# Orsini.net
KiCad netlist of a schematic drawn in EAGLE
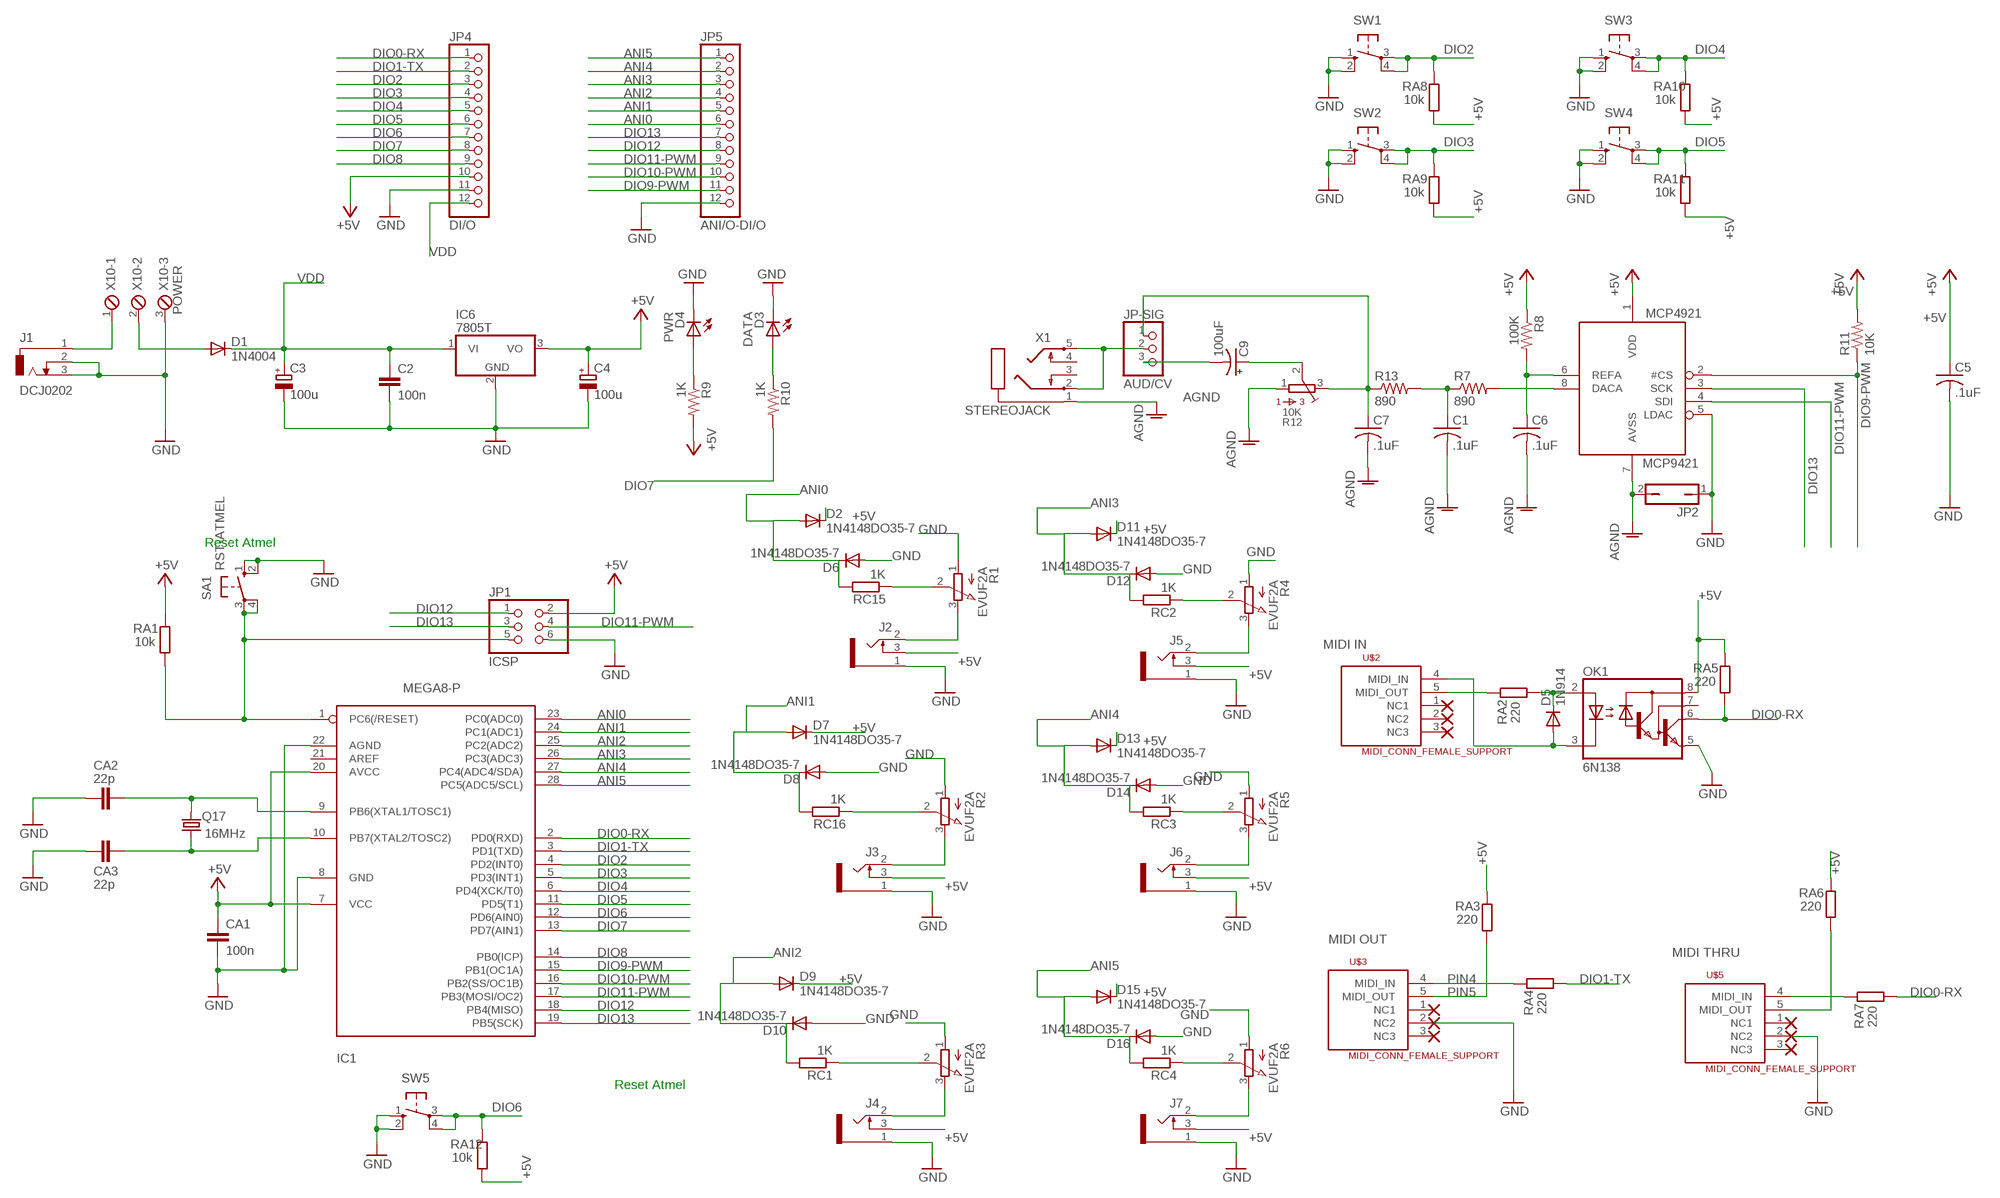
[diagram p0: schematic, sheet 1]

(export (version "E")
  (design (tool "Eeschema 10.0.6"))
  (components
    (comp (ref "C1")
      (value ".1uF")
      (footprint "eagle-import:C050-025X075")
      (libsource (lib "eagle-import") (part "C-US050-025X075"))
    )
    (comp (ref "C2")
      (value "100n")
      (footprint "eagle-import:C050-025X075")
      (libsource (lib "eagle-import") (part "C-EU050-025X075"))
    )
    (comp (ref "C3")
      (value "100u")
      (footprint "eagle-import:E2,5-7")
      (libsource (lib "eagle-import") (part "CPOL-EUE2.5-7"))
    )
    (comp (ref "C4")
      (value "100u")
      (footprint "eagle-import:E2,5-7")
      (libsource (lib "eagle-import") (part "CPOL-EUE2.5-7"))
    )
    (comp (ref "C5")
      (value ".1uF")
      (footprint "eagle-import:C025-025X050")
      (libsource (lib "eagle-import") (part "C-US025-025X050"))
    )
    (comp (ref "C6")
      (value ".1uF")
      (footprint "eagle-import:C025-025X050")
      (libsource (lib "eagle-import") (part "C-US025-025X050"))
    )
    (comp (ref "C7")
      (value ".1uF")
      (footprint "eagle-import:C050-025X075")
      (libsource (lib "eagle-import") (part "C-US050-025X075"))
    )
    (comp (ref "C9")
      (value "100uF")
      (footprint "eagle-import:E2,5-5")
      (libsource (lib "eagle-import") (part "CPOL-USE2.5-5"))
    )
    (comp (ref "CA1")
      (value "100n")
      (footprint "eagle-import:C050-025X075")
      (libsource (lib "eagle-import") (part "C-EU050-025X075"))
    )
    (comp (ref "CA2")
      (value "22p")
      (footprint "eagle-import:C050-025X075")
      (libsource (lib "eagle-import") (part "C-EU050-025X075"))
    )
    (comp (ref "CA3")
      (value "22p")
      (footprint "eagle-import:C050-025X075")
      (libsource (lib "eagle-import") (part "C-EU050-025X075"))
    )
    (comp (ref "D1")
      (value "1N4004")
      (footprint "eagle-import:DO41-10")
      (libsource (lib "eagle-import") (part "1N4004"))
    )
    (comp (ref "D2")
      (value "1N4148DO35-7")
      (footprint "eagle-import:DO35-7")
      (libsource (lib "eagle-import") (part "1N4148DO35-7"))
    )
    (comp (ref "D3")
      (value "DATA")
      (footprint "eagle-import:LED4MM")
      (libsource (lib "eagle-import") (part "HLMP-M"))
    )
    (comp (ref "D4")
      (value "PWR")
      (footprint "eagle-import:LED4MM")
      (libsource (lib "eagle-import") (part "HLMP-M"))
    )
    (comp (ref "D5")
      (value "1N914")
      (footprint "eagle-import:DO34-7")
      (libsource (lib "eagle-import") (part "BAS15"))
    )
    (comp (ref "D6")
      (value "1N4148DO35-7")
      (footprint "eagle-import:DO35-7")
      (libsource (lib "eagle-import") (part "1N4148DO35-7"))
    )
    (comp (ref "D7")
      (value "1N4148DO35-7")
      (footprint "eagle-import:DO35-7")
      (libsource (lib "eagle-import") (part "1N4148DO35-7"))
    )
    (comp (ref "D8")
      (value "1N4148DO35-7")
      (footprint "eagle-import:DO35-7")
      (libsource (lib "eagle-import") (part "1N4148DO35-7"))
    )
    (comp (ref "D9")
      (value "1N4148DO35-7")
      (footprint "eagle-import:DO35-7")
      (libsource (lib "eagle-import") (part "1N4148DO35-7"))
    )
    (comp (ref "D10")
      (value "1N4148DO35-7")
      (footprint "eagle-import:DO35-7")
      (libsource (lib "eagle-import") (part "1N4148DO35-7"))
    )
    (comp (ref "D11")
      (value "1N4148DO35-7")
      (footprint "eagle-import:DO35-7")
      (libsource (lib "eagle-import") (part "1N4148DO35-7"))
    )
    (comp (ref "D12")
      (value "1N4148DO35-7")
      (footprint "eagle-import:DO35-7")
      (libsource (lib "eagle-import") (part "1N4148DO35-7"))
    )
    (comp (ref "D13")
      (value "1N4148DO35-7")
      (footprint "eagle-import:DO35-7")
      (libsource (lib "eagle-import") (part "1N4148DO35-7"))
    )
    (comp (ref "D14")
      (value "1N4148DO35-7")
      (footprint "eagle-import:DO35-7")
      (libsource (lib "eagle-import") (part "1N4148DO35-7"))
    )
    (comp (ref "D15")
      (value "1N4148DO35-7")
      (footprint "eagle-import:DO35-7")
      (libsource (lib "eagle-import") (part "1N4148DO35-7"))
    )
    (comp (ref "D16")
      (value "1N4148DO35-7")
      (footprint "eagle-import:DO35-7")
      (libsource (lib "eagle-import") (part "1N4148DO35-7"))
    )
    (comp (ref "IC1")
      (value "MEGA8-P")
      (footprint "eagle-import:DIL28-3")
      (libsource (lib "eagle-import") (part "MEGA8-P"))
    )
    (comp (ref "IC6")
      (value "7805T")
      (footprint "eagle-import:TO220H")
      (libsource (lib "eagle-import") (part "78T05"))
    )
    (comp (ref "J1")
      (value "DCJ0202")
      (footprint "eagle-import:DCJ0202")
      (libsource (lib "eagle-import") (part "DCJ0202"))
    )
    (comp (ref "J2")
      (value "1502_03SLOTTED")
      (footprint "eagle-import:1502_03_SLOTTED")
      (libsource (lib "eagle-import") (part "1502_03SLOTTED"))
    )
    (comp (ref "J3")
      (value "1502_03SLOTTED")
      (footprint "eagle-import:1502_03_SLOTTED")
      (libsource (lib "eagle-import") (part "1502_03SLOTTED"))
    )
    (comp (ref "J4")
      (value "1502_03SLOTTED")
      (footprint "eagle-import:1502_03_SLOTTED")
      (libsource (lib "eagle-import") (part "1502_03SLOTTED"))
    )
    (comp (ref "J5")
      (value "1502_03SLOTTED")
      (footprint "eagle-import:1502_03_SLOTTED")
      (libsource (lib "eagle-import") (part "1502_03SLOTTED"))
    )
    (comp (ref "J6")
      (value "1502_03SLOTTED")
      (footprint "eagle-import:1502_03_SLOTTED")
      (libsource (lib "eagle-import") (part "1502_03SLOTTED"))
    )
    (comp (ref "J7")
      (value "1502_03SLOTTED")
      (footprint "eagle-import:1502_03_SLOTTED")
      (libsource (lib "eagle-import") (part "1502_03SLOTTED"))
    )
    (comp (ref "JP-SIG")
      (value "AUD/CV")
      (footprint "eagle-import:1X03")
      (libsource (lib "eagle-import") (part "PINHD-1X3"))
    )
    (comp (ref "JP1")
      (value "ICSP")
      (footprint "eagle-import:2X03")
      (libsource (lib "eagle-import") (part "PINHD-2X3"))
    )
    (comp (ref "JP2")
      (value "JP1Q")
      (footprint "eagle-import:JP1")
      (libsource (lib "eagle-import") (part "JP1Q"))
    )
    (comp (ref "JP4")
      (value "DI/O")
      (footprint "eagle-import:1X12")
      (libsource (lib "eagle-import") (part "PINHD-1X12"))
    )
    (comp (ref "JP5")
      (value "ANI/O-DI/O")
      (footprint "eagle-import:1X12")
      (libsource (lib "eagle-import") (part "PINHD-1X12"))
    )
    (comp (ref "MCP4921")
      (value "MCP9421")
      (footprint "eagle-import:DIL08")
      (libsource (lib "eagle-import") (part "MCP9421"))
    )
    (comp (ref "OK1")
      (value "6N138")
      (footprint "eagle-import:DIL08")
      (fields (field (name "MF") "VISHAY/TELEFUNKEN"))
      (libsource (lib "eagle-import") (part "6N138"))
    )
    (comp (ref "Q17")
      (value "16MHz")
      (footprint "eagle-import:HC49_S")
      (libsource (lib "eagle-import") (part "CRYSTALHC49S"))
    )
    (comp (ref "R1")
      (value "EVUF2A")
      (footprint "eagle-import:EVUF")
      (libsource (lib "eagle-import") (part "EVUAF2"))
    )
    (comp (ref "R2")
      (value "EVUF2A")
      (footprint "eagle-import:EVUF")
      (libsource (lib "eagle-import") (part "EVUAF2"))
    )
    (comp (ref "R3")
      (value "EVUF2A")
      (footprint "eagle-import:EVUF")
      (libsource (lib "eagle-import") (part "EVUAF2"))
    )
    (comp (ref "R4")
      (value "EVUF2A")
      (footprint "eagle-import:EVUF")
      (libsource (lib "eagle-import") (part "EVUAF2"))
    )
    (comp (ref "R5")
      (value "EVUF2A")
      (footprint "eagle-import:EVUF")
      (libsource (lib "eagle-import") (part "EVUAF2"))
    )
    (comp (ref "R6")
      (value "EVUF2A")
      (footprint "eagle-import:EVUF")
      (libsource (lib "eagle-import") (part "EVUAF2"))
    )
    (comp (ref "R7")
      (value "890")
      (footprint "eagle-import:0207_7")
      (libsource (lib "eagle-import") (part "R-US_0207/7"))
    )
    (comp (ref "R8")
      (value "100K")
      (footprint "eagle-import:0207_7")
      (libsource (lib "eagle-import") (part "R-US_0207/7"))
    )
    (comp (ref "R9")
      (value "1K")
      (footprint "eagle-import:0207_7")
      (libsource (lib "eagle-import") (part "R-US_0207/7"))
    )
    (comp (ref "R10")
      (value "1K")
      (footprint "eagle-import:0207_7")
      (libsource (lib "eagle-import") (part "R-US_0207/7"))
    )
    (comp (ref "R11")
      (value "10K")
      (footprint "eagle-import:0207_10")
      (libsource (lib "eagle-import") (part "R-US_0207/10"))
    )
    (comp (ref "R12")
      (value "10K")
      (footprint "eagle-import:3386F")
      (libsource (lib "eagle-import") (part "3386-F"))
    )
    (comp (ref "R13")
      (value "890")
      (footprint "eagle-import:0207_7")
      (libsource (lib "eagle-import") (part "R-US_0207/7"))
    )
    (comp (ref "RA1")
      (value "10k")
      (footprint "eagle-import:0207_10")
      (libsource (lib "eagle-import") (part "R-EU_0207/10"))
    )
    (comp (ref "RA2")
      (value "220")
      (footprint "eagle-import:0207_10")
      (libsource (lib "eagle-import") (part "R-EU_0207/10"))
    )
    (comp (ref "RA3")
      (value "220")
      (footprint "eagle-import:0207_10")
      (libsource (lib "eagle-import") (part "R-EU_0207/10"))
    )
    (comp (ref "RA4")
      (value "220")
      (footprint "eagle-import:0207_10")
      (libsource (lib "eagle-import") (part "R-EU_0207/10"))
    )
    (comp (ref "RA5")
      (value "220")
      (footprint "eagle-import:0207_10")
      (libsource (lib "eagle-import") (part "R-EU_0207/10"))
    )
    (comp (ref "RA6")
      (value "220")
      (footprint "eagle-import:0207_10")
      (libsource (lib "eagle-import") (part "R-EU_0207/10"))
    )
    (comp (ref "RA7")
      (value "220")
      (footprint "eagle-import:0207_10")
      (libsource (lib "eagle-import") (part "R-EU_0207/10"))
    )
    (comp (ref "RA8")
      (value "10k")
      (footprint "eagle-import:0207_10")
      (libsource (lib "eagle-import") (part "R-EU_0207/10"))
    )
    (comp (ref "RA9")
      (value "10k")
      (footprint "eagle-import:0207_10")
      (libsource (lib "eagle-import") (part "R-EU_0207/10"))
    )
    (comp (ref "RA10")
      (value "10k")
      (footprint "eagle-import:0207_10")
      (libsource (lib "eagle-import") (part "R-EU_0207/10"))
    )
    (comp (ref "RA11")
      (value "10k")
      (footprint "eagle-import:0207_10")
      (libsource (lib "eagle-import") (part "R-EU_0207/10"))
    )
    (comp (ref "RA12")
      (value "10k")
      (footprint "eagle-import:0207_10")
      (libsource (lib "eagle-import") (part "R-EU_0207/10"))
    )
    (comp (ref "RC1")
      (value "1K")
      (footprint "eagle-import:0207_10")
      (libsource (lib "eagle-import") (part "R-EU_0207/10"))
    )
    (comp (ref "RC2")
      (value "1K")
      (footprint "eagle-import:0207_10")
      (libsource (lib "eagle-import") (part "R-EU_0207/10"))
    )
    (comp (ref "RC3")
      (value "1K")
      (footprint "eagle-import:0207_10")
      (libsource (lib "eagle-import") (part "R-EU_0207/10"))
    )
    (comp (ref "RC4")
      (value "1K")
      (footprint "eagle-import:0207_10")
      (libsource (lib "eagle-import") (part "R-EU_0207/10"))
    )
    (comp (ref "RC15")
      (value "1K")
      (footprint "eagle-import:0207_10")
      (libsource (lib "eagle-import") (part "R-EU_0207/10"))
    )
    (comp (ref "RC16")
      (value "1K")
      (footprint "eagle-import:0207_10")
      (libsource (lib "eagle-import") (part "R-EU_0207/10"))
    )
    (comp (ref "SA1")
      (value "RST-ATMEL")
      (footprint "eagle-import:B3F-10XX")
      (libsource (lib "eagle-import") (part "10-XX"))
    )
    (comp (ref "SW1")
      (value "40-XX")
      (footprint "eagle-import:B3F-40XX")
      (libsource (lib "eagle-import") (part "40-XX"))
    )
    (comp (ref "SW2")
      (value "40-XX")
      (footprint "eagle-import:B3F-40XX")
      (libsource (lib "eagle-import") (part "40-XX"))
    )
    (comp (ref "SW3")
      (value "40-XX")
      (footprint "eagle-import:B3F-40XX")
      (libsource (lib "eagle-import") (part "40-XX"))
    )
    (comp (ref "SW4")
      (value "40-XX")
      (footprint "eagle-import:B3F-40XX")
      (libsource (lib "eagle-import") (part "40-XX"))
    )
    (comp (ref "SW5")
      (value "40-XX")
      (footprint "eagle-import:B3F-40XX")
      (libsource (lib "eagle-import") (part "40-XX"))
    )
    (comp (ref "U$2")
      (value "MIDI_CONN_FEMALE_SUPPORT")
      (footprint "eagle-import:DIN_5_FEMALE_SUPPORT")
      (libsource (lib "eagle-import") (part "MIDI_CONN_FEMALE_SUPPORT"))
    )
    (comp (ref "U$3")
      (value "MIDI_CONN_FEMALE_SUPPORT")
      (footprint "eagle-import:DIN_5_FEMALE_SUPPORT")
      (libsource (lib "eagle-import") (part "MIDI_CONN_FEMALE_SUPPORT"))
    )
    (comp (ref "U$5")
      (value "MIDI_CONN_FEMALE_SUPPORT")
      (footprint "eagle-import:DIN_5_FEMALE_SUPPORT")
      (libsource (lib "eagle-import") (part "MIDI_CONN_FEMALE_SUPPORT"))
    )
    (comp (ref "X1")
      (value "STEREOJACK")
      (footprint "eagle-import:STX3001")
      (libsource (lib "eagle-import") (part "STEREOJACK"))
    )
    (comp (ref "X10")
      (value "POWER")
      (footprint "eagle-import:3POL254")
      (libsource (lib "eagle-import") (part "MPT3"))
    )
  )
  (nets
    (net (code "1") (name "+5V") (class "Default")
      (node (ref "C4") (pin "+") (pinfunction "+_+") (pintype "passive"))
      (node (ref "C5") (pin "1") (pinfunction "1_1") (pintype "passive"))
      (node (ref "CA1") (pin "1") (pinfunction "1_1") (pintype "passive"))
      (node (ref "D11") (pin "C") (pinfunction "C_C") (pintype "passive"))
      (node (ref "D13") (pin "C") (pinfunction "C_C") (pintype "passive"))
      (node (ref "D15") (pin "C") (pinfunction "C_C") (pintype "passive"))
      (node (ref "D2") (pin "C") (pinfunction "C_C") (pintype "passive"))
      (node (ref "D7") (pin "C") (pinfunction "C_C") (pintype "passive"))
      (node (ref "D9") (pin "C") (pinfunction "C_C") (pintype "passive"))
      (node (ref "IC1") (pin "20") (pinfunction "AVCC_20") (pintype "power_in"))
      (node (ref "IC1") (pin "7") (pinfunction "VCC_7") (pintype "power_in"))
      (node (ref "IC6") (pin "3") (pinfunction "VO_3") (pintype "passive"))
      (node (ref "J2") (pin "3") (pinfunction "3_3") (pintype "passive"))
      (node (ref "J3") (pin "3") (pinfunction "3_3") (pintype "passive"))
      (node (ref "J4") (pin "3") (pinfunction "3_3") (pintype "passive"))
      (node (ref "J5") (pin "3") (pinfunction "3_3") (pintype "passive"))
      (node (ref "J6") (pin "3") (pinfunction "3_3") (pintype "passive"))
      (node (ref "J7") (pin "3") (pinfunction "3_3") (pintype "passive"))
      (node (ref "JP1") (pin "2") (pinfunction "2_2") (pintype "passive"))
      (node (ref "JP4") (pin "10") (pinfunction "10_10") (pintype "passive"))
      (node (ref "MCP4921") (pin "1") (pinfunction "VDD_1") (pintype "power_in"))
      (node (ref "OK1") (pin "8") (pinfunction "VCC_8") (pintype "passive"))
      (node (ref "R11") (pin "2") (pinfunction "2_2") (pintype "passive"))
      (node (ref "R8") (pin "1") (pinfunction "1_1") (pintype "passive"))
      (node (ref "R9") (pin "2") (pinfunction "2_2") (pintype "passive"))
      (node (ref "RA1") (pin "1") (pinfunction "1_1") (pintype "passive"))
      (node (ref "RA10") (pin "2") (pinfunction "2_2") (pintype "passive"))
      (node (ref "RA11") (pin "2") (pinfunction "2_2") (pintype "passive"))
      (node (ref "RA12") (pin "2") (pinfunction "2_2") (pintype "passive"))
      (node (ref "RA3") (pin "1") (pinfunction "1_1") (pintype "passive"))
      (node (ref "RA5") (pin "1") (pinfunction "1_1") (pintype "passive"))
      (node (ref "RA6") (pin "1") (pinfunction "1_1") (pintype "passive"))
      (node (ref "RA8") (pin "2") (pinfunction "2_2") (pintype "passive"))
      (node (ref "RA9") (pin "2") (pinfunction "2_2") (pintype "passive"))
    )
    (net (code "2") (name "/ANI0") (class "Default")
      (node (ref "D2") (pin "A") (pinfunction "A_A") (pintype "passive"))
      (node (ref "D6") (pin "C") (pinfunction "C_C") (pintype "passive"))
      (node (ref "IC1") (pin "23") (pinfunction "PC0(ADC0)_23") (pintype "bidirectional"))
      (node (ref "JP5") (pin "6") (pinfunction "6_6") (pintype "passive"))
      (node (ref "RC15") (pin "2") (pinfunction "2_2") (pintype "passive"))
    )
    (net (code "3") (name "/ANI1") (class "Default")
      (node (ref "D7") (pin "A") (pinfunction "A_A") (pintype "passive"))
      (node (ref "D8") (pin "C") (pinfunction "C_C") (pintype "passive"))
      (node (ref "IC1") (pin "24") (pinfunction "PC1(ADC1)_24") (pintype "bidirectional"))
      (node (ref "JP5") (pin "5") (pinfunction "5_5") (pintype "passive"))
      (node (ref "RC16") (pin "2") (pinfunction "2_2") (pintype "passive"))
    )
    (net (code "4") (name "/ANI2") (class "Default")
      (node (ref "D10") (pin "C") (pinfunction "C_C") (pintype "passive"))
      (node (ref "D9") (pin "A") (pinfunction "A_A") (pintype "passive"))
      (node (ref "IC1") (pin "25") (pinfunction "PC2(ADC2)_25") (pintype "bidirectional"))
      (node (ref "JP5") (pin "4") (pinfunction "4_4") (pintype "passive"))
      (node (ref "RC1") (pin "2") (pinfunction "2_2") (pintype "passive"))
    )
    (net (code "5") (name "/ANI3") (class "Default")
      (node (ref "D11") (pin "A") (pinfunction "A_A") (pintype "passive"))
      (node (ref "D12") (pin "C") (pinfunction "C_C") (pintype "passive"))
      (node (ref "IC1") (pin "26") (pinfunction "PC3(ADC3)_26") (pintype "bidirectional"))
      (node (ref "JP5") (pin "3") (pinfunction "3_3") (pintype "passive"))
      (node (ref "RC2") (pin "2") (pinfunction "2_2") (pintype "passive"))
    )
    (net (code "6") (name "/ANI4") (class "Default")
      (node (ref "D13") (pin "A") (pinfunction "A_A") (pintype "passive"))
      (node (ref "D14") (pin "C") (pinfunction "C_C") (pintype "passive"))
      (node (ref "IC1") (pin "27") (pinfunction "PC4(ADC4/SDA)_27") (pintype "bidirectional"))
      (node (ref "JP5") (pin "2") (pinfunction "2_2") (pintype "passive"))
      (node (ref "RC3") (pin "2") (pinfunction "2_2") (pintype "passive"))
    )
    (net (code "7") (name "/ANI5") (class "Default")
      (node (ref "D15") (pin "A") (pinfunction "A_A") (pintype "passive"))
      (node (ref "D16") (pin "C") (pinfunction "C_C") (pintype "passive"))
      (node (ref "IC1") (pin "28") (pinfunction "PC5(ADC5/SCL)_28") (pintype "bidirectional"))
      (node (ref "JP5") (pin "1") (pinfunction "1_1") (pintype "passive"))
      (node (ref "RC4") (pin "2") (pinfunction "2_2") (pintype "passive"))
    )
    (net (code "8") (name "/DIO0-RX") (class "Default")
      (node (ref "IC1") (pin "2") (pinfunction "PD0(RXD)_2") (pintype "bidirectional"))
      (node (ref "JP4") (pin "1") (pinfunction "1_1") (pintype "passive"))
      (node (ref "OK1") (pin "6") (pinfunction "VO_6") (pintype "passive"))
      (node (ref "RA5") (pin "2") (pinfunction "2_2") (pintype "passive"))
      (node (ref "RA7") (pin "2") (pinfunction "2_2") (pintype "passive"))
    )
    (net (code "9") (name "/DIO1-TX") (class "Default")
      (node (ref "IC1") (pin "3") (pinfunction "PD1(TXD)_3") (pintype "bidirectional"))
      (node (ref "JP4") (pin "2") (pinfunction "2_2") (pintype "passive"))
      (node (ref "RA4") (pin "2") (pinfunction "2_2") (pintype "passive"))
    )
    (net (code "10") (name "/DIO2") (class "Default")
      (node (ref "IC1") (pin "4") (pinfunction "PD2(INT0)_4") (pintype "bidirectional"))
      (node (ref "JP4") (pin "3") (pinfunction "3_3") (pintype "passive"))
      (node (ref "RA8") (pin "1") (pinfunction "1_1") (pintype "passive"))
      (node (ref "SW1") (pin "3") (pinfunction "P_3") (pintype "passive"))
      (node (ref "SW1") (pin "4") (pinfunction "P1_4") (pintype "passive"))
    )
    (net (code "11") (name "/DIO3") (class "Default")
      (node (ref "IC1") (pin "5") (pinfunction "PD3(INT1)_5") (pintype "bidirectional"))
      (node (ref "JP4") (pin "4") (pinfunction "4_4") (pintype "passive"))
      (node (ref "RA9") (pin "1") (pinfunction "1_1") (pintype "passive"))
      (node (ref "SW2") (pin "3") (pinfunction "P_3") (pintype "passive"))
      (node (ref "SW2") (pin "4") (pinfunction "P1_4") (pintype "passive"))
    )
    (net (code "12") (name "/DIO4") (class "Default")
      (node (ref "IC1") (pin "6") (pinfunction "PD4(XCK/T0)_6") (pintype "bidirectional"))
      (node (ref "JP4") (pin "5") (pinfunction "5_5") (pintype "passive"))
      (node (ref "RA10") (pin "1") (pinfunction "1_1") (pintype "passive"))
      (node (ref "SW3") (pin "3") (pinfunction "P_3") (pintype "passive"))
      (node (ref "SW3") (pin "4") (pinfunction "P1_4") (pintype "passive"))
    )
    (net (code "13") (name "/DIO5") (class "Default")
      (node (ref "IC1") (pin "11") (pinfunction "PD5(T1)_11") (pintype "bidirectional"))
      (node (ref "JP4") (pin "6") (pinfunction "6_6") (pintype "passive"))
      (node (ref "RA11") (pin "1") (pinfunction "1_1") (pintype "passive"))
      (node (ref "SW4") (pin "3") (pinfunction "P_3") (pintype "passive"))
      (node (ref "SW4") (pin "4") (pinfunction "P1_4") (pintype "passive"))
    )
    (net (code "14") (name "/DIO6") (class "Default")
      (node (ref "IC1") (pin "12") (pinfunction "PD6(AIN0)_12") (pintype "bidirectional"))
      (node (ref "JP4") (pin "7") (pinfunction "7_7") (pintype "passive"))
      (node (ref "RA12") (pin "1") (pinfunction "1_1") (pintype "passive"))
      (node (ref "SW5") (pin "3") (pinfunction "P_3") (pintype "passive"))
      (node (ref "SW5") (pin "4") (pinfunction "P1_4") (pintype "passive"))
    )
    (net (code "15") (name "/DIO7") (class "Default")
      (node (ref "IC1") (pin "13") (pinfunction "PD7(AIN1)_13") (pintype "bidirectional"))
      (node (ref "JP4") (pin "8") (pinfunction "8_8") (pintype "passive"))
      (node (ref "R10") (pin "2") (pinfunction "2_2") (pintype "passive"))
    )
    (net (code "16") (name "/DIO8") (class "Default")
      (node (ref "IC1") (pin "14") (pinfunction "PB0(ICP)_14") (pintype "bidirectional"))
      (node (ref "JP4") (pin "9") (pinfunction "9_9") (pintype "passive"))
    )
    (net (code "17") (name "/DIO9-PWM") (class "Default")
      (node (ref "IC1") (pin "15") (pinfunction "PB1(OC1A)_15") (pintype "bidirectional"))
      (node (ref "JP5") (pin "11") (pinfunction "11_11") (pintype "passive"))
      (node (ref "MCP4921") (pin "2") (pinfunction "#CS_2") (pintype "input"))
      (node (ref "R11") (pin "1") (pinfunction "1_1") (pintype "passive"))
    )
    (net (code "18") (name "/DIO10-PWM") (class "Default")
      (node (ref "IC1") (pin "16") (pinfunction "PB2(SS/OC1B)_16") (pintype "bidirectional"))
      (node (ref "JP5") (pin "10") (pinfunction "10_10") (pintype "passive"))
    )
    (net (code "19") (name "/DIO11-PWM") (class "Default")
      (node (ref "IC1") (pin "17") (pinfunction "PB3(MOSI/OC2)_17") (pintype "bidirectional"))
      (node (ref "JP1") (pin "4") (pinfunction "4_4") (pintype "passive"))
      (node (ref "JP5") (pin "9") (pinfunction "9_9") (pintype "passive"))
      (node (ref "MCP4921") (pin "4") (pinfunction "SDI_4") (pintype "input"))
    )
    (net (code "20") (name "/DIO12") (class "Default")
      (node (ref "IC1") (pin "18") (pinfunction "PB4(MISO)_18") (pintype "bidirectional"))
      (node (ref "JP1") (pin "1") (pinfunction "1_1") (pintype "passive"))
      (node (ref "JP5") (pin "8") (pinfunction "8_8") (pintype "passive"))
    )
    (net (code "21") (name "/DIO13") (class "Default")
      (node (ref "IC1") (pin "19") (pinfunction "PB5(SCK)_19") (pintype "bidirectional"))
      (node (ref "JP1") (pin "3") (pinfunction "3_3") (pintype "passive"))
      (node (ref "JP5") (pin "7") (pinfunction "7_7") (pintype "passive"))
      (node (ref "MCP4921") (pin "3") (pinfunction "SCK_3") (pintype "input"))
    )
    (net (code "22") (name "/VDD") (class "Default")
      (node (ref "C2") (pin "1") (pinfunction "1_1") (pintype "passive"))
      (node (ref "C3") (pin "+") (pinfunction "+_+") (pintype "passive"))
      (node (ref "D1") (pin "C") (pinfunction "C_C") (pintype "passive"))
      (node (ref "IC6") (pin "1") (pinfunction "VI_1") (pintype "input"))
      (node (ref "JP4") (pin "12") (pinfunction "12_12") (pintype "passive"))
    )
    (net (code "23") (name "AGND") (class "Default")
      (node (ref "C1") (pin "2") (pinfunction "2_2") (pintype "passive"))
      (node (ref "C6") (pin "2") (pinfunction "2_2") (pintype "passive"))
      (node (ref "C7") (pin "2") (pinfunction "2_2") (pintype "passive"))
      (node (ref "JP2") (pin "2") (pinfunction "2_2") (pintype "passive"))
      (node (ref "MCP4921") (pin "7") (pinfunction "AVSS_7") (pintype "power_in"))
      (node (ref "R12") (pin "1") (pinfunction "1_1") (pintype "passive"))
      (node (ref "X1") (pin "1") (pinfunction "1_1") (pintype "passive"))
    )
    (net (code "24") (name "GND") (class "Default")
      (node (ref "C2") (pin "2") (pinfunction "2_2") (pintype "passive"))
      (node (ref "C3") (pin "-") (pinfunction "-_-") (pintype "passive"))
      (node (ref "C4") (pin "-") (pinfunction "-_-") (pintype "passive"))
      (node (ref "C5") (pin "2") (pinfunction "2_2") (pintype "passive"))
      (node (ref "CA1") (pin "2") (pinfunction "2_2") (pintype "passive"))
      (node (ref "CA2") (pin "2") (pinfunction "2_2") (pintype "passive"))
      (node (ref "CA3") (pin "2") (pinfunction "2_2") (pintype "passive"))
      (node (ref "D10") (pin "A") (pinfunction "A_A") (pintype "passive"))
      (node (ref "D12") (pin "A") (pinfunction "A_A") (pintype "passive"))
      (node (ref "D14") (pin "A") (pinfunction "A_A") (pintype "passive"))
      (node (ref "D16") (pin "A") (pinfunction "A_A") (pintype "passive"))
      (node (ref "D3") (pin "A") (pinfunction "C_A") (pintype "passive"))
      (node (ref "D4") (pin "A") (pinfunction "C_A") (pintype "passive"))
      (node (ref "D6") (pin "A") (pinfunction "A_A") (pintype "passive"))
      (node (ref "D8") (pin "A") (pinfunction "A_A") (pintype "passive"))
      (node (ref "IC1") (pin "22") (pinfunction "AGND_22") (pintype "power_in"))
      (node (ref "IC1") (pin "8") (pinfunction "GND_8") (pintype "power_in"))
      (node (ref "IC6") (pin "2") (pinfunction "GND_2") (pintype "passive"))
      (node (ref "J1") (pin "2") (pinfunction "2_2") (pintype "passive"))
      (node (ref "J1") (pin "3") (pinfunction "3_3") (pintype "passive"))
      (node (ref "J2") (pin "1") (pinfunction "1_1") (pintype "passive"))
      (node (ref "J3") (pin "1") (pinfunction "1_1") (pintype "passive"))
      (node (ref "J4") (pin "1") (pinfunction "1_1") (pintype "passive"))
      (node (ref "J5") (pin "1") (pinfunction "1_1") (pintype "passive"))
      (node (ref "J6") (pin "1") (pinfunction "1_1") (pintype "passive"))
      (node (ref "J7") (pin "1") (pinfunction "1_1") (pintype "passive"))
      (node (ref "JP1") (pin "6") (pinfunction "6_6") (pintype "passive"))
      (node (ref "JP2") (pin "1") (pinfunction "1_1") (pintype "passive"))
      (node (ref "JP4") (pin "11") (pinfunction "11_11") (pintype "passive"))
      (node (ref "JP5") (pin "12") (pinfunction "12_12") (pintype "passive"))
      (node (ref "MCP4921") (pin "5") (pinfunction "LDAC_5") (pintype "input"))
      (node (ref "OK1") (pin "5") (pinfunction "GND_5") (pintype "passive"))
      (node (ref "R1") (pin "1") (pinfunction "A_1") (pintype "passive"))
      (node (ref "R2") (pin "1") (pinfunction "A_1") (pintype "passive"))
      (node (ref "R3") (pin "1") (pinfunction "A_1") (pintype "passive"))
      (node (ref "R4") (pin "1") (pinfunction "A_1") (pintype "passive"))
      (node (ref "R5") (pin "1") (pinfunction "A_1") (pintype "passive"))
      (node (ref "R6") (pin "1") (pinfunction "A_1") (pintype "passive"))
      (node (ref "SA1") (pin "1") (pinfunction "S_1") (pintype "passive"))
      (node (ref "SA1") (pin "2") (pinfunction "S1_2") (pintype "passive"))
      (node (ref "SW1") (pin "1") (pinfunction "S_1") (pintype "passive"))
      (node (ref "SW1") (pin "2") (pinfunction "S1_2") (pintype "passive"))
      (node (ref "SW2") (pin "1") (pinfunction "S_1") (pintype "passive"))
      (node (ref "SW2") (pin "2") (pinfunction "S1_2") (pintype "passive"))
      (node (ref "SW3") (pin "1") (pinfunction "S_1") (pintype "passive"))
      (node (ref "SW3") (pin "2") (pinfunction "S1_2") (pintype "passive"))
      (node (ref "SW4") (pin "1") (pinfunction "S_1") (pintype "passive"))
      (node (ref "SW4") (pin "2") (pinfunction "S1_2") (pintype "passive"))
      (node (ref "SW5") (pin "1") (pinfunction "S_1") (pintype "passive"))
      (node (ref "SW5") (pin "2") (pinfunction "S1_2") (pintype "passive"))
      (node (ref "U$3") (pin "2") (pinfunction "NC2_2") (pintype "bidirectional"))
      (node (ref "U$5") (pin "2") (pinfunction "NC2_2") (pintype "bidirectional"))
      (node (ref "X10") (pin "3") (pinfunction "1_3") (pintype "passive"))
    )
    (net (code "25") (name "Net-(C1-Pad1)") (class "Default")
      (node (ref "C1") (pin "1") (pinfunction "1_1") (pintype "passive"))
      (node (ref "R13") (pin "2") (pinfunction "2_2") (pintype "passive"))
      (node (ref "R7") (pin "1") (pinfunction "1_1") (pintype "passive"))
    )
    (net (code "26") (name "Net-(C7-Pad1)") (class "Default")
      (node (ref "C7") (pin "1") (pinfunction "1_1") (pintype "passive"))
      (node (ref "JP-SIG") (pin "1") (pinfunction "1_1") (pintype "passive"))
      (node (ref "R12") (pin "3") (pinfunction "3_3") (pintype "passive"))
      (node (ref "R13") (pin "1") (pinfunction "1_1") (pintype "passive"))
    )
    (net (code "27") (name "Net-(C9-Pad+)") (class "Default")
      (node (ref "C9") (pin "+") (pinfunction "+_+") (pintype "passive"))
      (node (ref "R12") (pin "2") (pinfunction "2_2") (pintype "passive"))
    )
    (net (code "28") (name "Net-(C9-Pad-)") (class "Default")
      (node (ref "C9") (pin "-") (pinfunction "-_-") (pintype "passive"))
      (node (ref "JP-SIG") (pin "3") (pinfunction "3_3") (pintype "passive"))
    )
    (net (code "29") (name "Net-(D3-A)") (class "Default")
      (node (ref "D3") (pin "K") (pinfunction "A_K") (pintype "passive"))
      (node (ref "R10") (pin "1") (pinfunction "1_1") (pintype "passive"))
    )
    (net (code "30") (name "Net-(D4-A)") (class "Default")
      (node (ref "D4") (pin "K") (pinfunction "A_K") (pintype "passive"))
      (node (ref "R9") (pin "1") (pinfunction "1_1") (pintype "passive"))
    )
    (net (code "31") (name "Net-(IC1-PB6(XTAL1{slash}TOSC1))") (class "Default")
      (node (ref "CA2") (pin "1") (pinfunction "1_1") (pintype "passive"))
      (node (ref "IC1") (pin "9") (pinfunction "PB6(XTAL1/TOSC1)_9") (pintype "bidirectional"))
      (node (ref "Q17") (pin "2") (pinfunction "2_2") (pintype "passive"))
    )
    (net (code "32") (name "Net-(IC1-PB7(XTAL2{slash}TOSC2))") (class "Default")
      (node (ref "CA3") (pin "1") (pinfunction "1_1") (pintype "passive"))
      (node (ref "IC1") (pin "10") (pinfunction "PB7(XTAL2/TOSC2)_10") (pintype "bidirectional"))
      (node (ref "Q17") (pin "1") (pinfunction "1_1") (pintype "passive"))
    )
    (net (code "33") (name "Net-(IC1-PC6({slash}RESET))") (class "Default")
      (node (ref "IC1") (pin "1") (pinfunction "PC6(/RESET)_1") (pintype "bidirectional"))
      (node (ref "JP1") (pin "5") (pinfunction "5_5") (pintype "passive"))
      (node (ref "RA1") (pin "2") (pinfunction "2_2") (pintype "passive"))
      (node (ref "SA1") (pin "3") (pinfunction "P_3") (pintype "passive"))
      (node (ref "SA1") (pin "4") (pinfunction "P1_4") (pintype "passive"))
    )
    (net (code "34") (name "Net-(J1-Pad1)") (class "Default")
      (node (ref "J1") (pin "1") (pinfunction "1_1") (pintype "passive"))
      (node (ref "X10") (pin "1") (pinfunction "1_1") (pintype "passive"))
    )
    (net (code "35") (name "Net-(JP-SIG-Pad2)") (class "Default")
      (node (ref "JP-SIG") (pin "2") (pinfunction "2_2") (pintype "passive"))
      (node (ref "X1") (pin "2") (pinfunction "2_2") (pintype "passive"))
      (node (ref "X1") (pin "5") (pinfunction "5_5") (pintype "passive"))
    )
    (net (code "36") (name "Net-(MCP4921-DACA)") (class "Default")
      (node (ref "MCP4921") (pin "8") (pinfunction "DACA_8") (pintype "output"))
      (node (ref "R7") (pin "2") (pinfunction "2_2") (pintype "passive"))
    )
    (net (code "37") (name "Net-(MCP4921-REFA)") (class "Default")
      (node (ref "C6") (pin "1") (pinfunction "1_1") (pintype "passive"))
      (node (ref "MCP4921") (pin "6") (pinfunction "REFA_6") (pintype "input"))
      (node (ref "R8") (pin "2") (pinfunction "2_2") (pintype "passive"))
    )
    (net (code "38") (name "Net-(OK1-A)") (class "Default")
      (node (ref "D5") (pin "C") (pinfunction "C_C") (pintype "passive"))
      (node (ref "OK1") (pin "2") (pinfunction "A_2") (pintype "passive"))
      (node (ref "RA2") (pin "2") (pinfunction "2_2") (pintype "passive"))
    )
    (net (code "39") (name "Net-(OK1-C)") (class "Default")
      (node (ref "D5") (pin "A") (pinfunction "A_A") (pintype "passive"))
      (node (ref "OK1") (pin "3") (pinfunction "C_3") (pintype "passive"))
      (node (ref "U$2") (pin "4") (pinfunction "MIDI_IN_4") (pintype "bidirectional"))
    )
    (net (code "40") (name "Net-(R1-E)") (class "Default")
      (node (ref "J2") (pin "2") (pinfunction "2_2") (pintype "passive"))
      (node (ref "R1") (pin "3") (pinfunction "E_3") (pintype "passive"))
    )
    (net (code "41") (name "Net-(R1-S)") (class "Default")
      (node (ref "R1") (pin "2") (pinfunction "S_2") (pintype "passive"))
      (node (ref "RC15") (pin "1") (pinfunction "1_1") (pintype "passive"))
    )
    (net (code "42") (name "Net-(R2-E)") (class "Default")
      (node (ref "J3") (pin "2") (pinfunction "2_2") (pintype "passive"))
      (node (ref "R2") (pin "3") (pinfunction "E_3") (pintype "passive"))
    )
    (net (code "43") (name "Net-(R2-S)") (class "Default")
      (node (ref "R2") (pin "2") (pinfunction "S_2") (pintype "passive"))
      (node (ref "RC16") (pin "1") (pinfunction "1_1") (pintype "passive"))
    )
    (net (code "44") (name "Net-(R3-E)") (class "Default")
      (node (ref "J4") (pin "2") (pinfunction "2_2") (pintype "passive"))
      (node (ref "R3") (pin "3") (pinfunction "E_3") (pintype "passive"))
    )
    (net (code "45") (name "Net-(R3-S)") (class "Default")
      (node (ref "R3") (pin "2") (pinfunction "S_2") (pintype "passive"))
      (node (ref "RC1") (pin "1") (pinfunction "1_1") (pintype "passive"))
    )
    (net (code "46") (name "Net-(R4-E)") (class "Default")
      (node (ref "J5") (pin "2") (pinfunction "2_2") (pintype "passive"))
      (node (ref "R4") (pin "3") (pinfunction "E_3") (pintype "passive"))
    )
    (net (code "47") (name "Net-(R4-S)") (class "Default")
      (node (ref "R4") (pin "2") (pinfunction "S_2") (pintype "passive"))
      (node (ref "RC2") (pin "1") (pinfunction "1_1") (pintype "passive"))
    )
    (net (code "48") (name "Net-(R5-E)") (class "Default")
      (node (ref "J6") (pin "2") (pinfunction "2_2") (pintype "passive"))
      (node (ref "R5") (pin "3") (pinfunction "E_3") (pintype "passive"))
    )
    (net (code "49") (name "Net-(R5-S)") (class "Default")
      (node (ref "R5") (pin "2") (pinfunction "S_2") (pintype "passive"))
      (node (ref "RC3") (pin "1") (pinfunction "1_1") (pintype "passive"))
    )
    (net (code "50") (name "Net-(R6-E)") (class "Default")
      (node (ref "J7") (pin "2") (pinfunction "2_2") (pintype "passive"))
      (node (ref "R6") (pin "3") (pinfunction "E_3") (pintype "passive"))
    )
    (net (code "51") (name "Net-(R6-S)") (class "Default")
      (node (ref "R6") (pin "2") (pinfunction "S_2") (pintype "passive"))
      (node (ref "RC4") (pin "1") (pinfunction "1_1") (pintype "passive"))
    )
    (net (code "52") (name "Net-(U$2-MIDI_OUT)") (class "Default")
      (node (ref "RA2") (pin "1") (pinfunction "1_1") (pintype "passive"))
      (node (ref "U$2") (pin "5") (pinfunction "MIDI_OUT_5") (pintype "bidirectional"))
    )
    (net (code "53") (name "Net-(U$3-MIDI_IN)") (class "Default")
      (node (ref "RA4") (pin "1") (pinfunction "1_1") (pintype "passive"))
      (node (ref "U$3") (pin "4") (pinfunction "MIDI_IN_4") (pintype "bidirectional"))
    )
    (net (code "54") (name "Net-(U$3-MIDI_OUT)") (class "Default")
      (node (ref "RA3") (pin "2") (pinfunction "2_2") (pintype "passive"))
      (node (ref "U$3") (pin "5") (pinfunction "MIDI_OUT_5") (pintype "bidirectional"))
    )
    (net (code "55") (name "Net-(U$5-MIDI_IN)") (class "Default")
      (node (ref "RA7") (pin "1") (pinfunction "1_1") (pintype "passive"))
      (node (ref "U$5") (pin "4") (pinfunction "MIDI_IN_4") (pintype "bidirectional"))
    )
    (net (code "56") (name "Net-(U$5-MIDI_OUT)") (class "Default")
      (node (ref "RA6") (pin "2") (pinfunction "2_2") (pintype "passive"))
      (node (ref "U$5") (pin "5") (pinfunction "MIDI_OUT_5") (pintype "bidirectional"))
    )
    (net (code "57") (name "Net-(X10B-1)") (class "Default")
      (node (ref "D1") (pin "A") (pinfunction "A_A") (pintype "passive"))
      (node (ref "X10") (pin "2") (pinfunction "1_2") (pintype "passive"))
    )
    (net (code "58") (name "unconnected-(IC1-AREF-Pad21)") (class "Default")
      (node (ref "IC1") (pin "21") (pinfunction "AREF_21") (pintype "passive"))
    )
    (net (code "59") (name "unconnected-(OK1-VB-Pad7)") (class "Default")
      (node (ref "OK1") (pin "7") (pinfunction "VB_7") (pintype "passive"))
    )
    (net (code "60") (name "unconnected-(U$2-NC1-Pad1)") (class "Default")
      (node (ref "U$2") (pin "1") (pinfunction "NC1_1") (pintype "bidirectional"))
    )
    (net (code "61") (name "unconnected-(U$2-NC2-Pad2)") (class "Default")
      (node (ref "U$2") (pin "2") (pinfunction "NC2_2") (pintype "bidirectional"))
    )
    (net (code "62") (name "unconnected-(U$2-NC3-Pad3)") (class "Default")
      (node (ref "U$2") (pin "3") (pinfunction "NC3_3") (pintype "bidirectional"))
    )
    (net (code "63") (name "unconnected-(U$3-NC1-Pad1)") (class "Default")
      (node (ref "U$3") (pin "1") (pinfunction "NC1_1") (pintype "bidirectional"))
    )
    (net (code "64") (name "unconnected-(U$3-NC3-Pad3)") (class "Default")
      (node (ref "U$3") (pin "3") (pinfunction "NC3_3") (pintype "bidirectional"))
    )
    (net (code "65") (name "unconnected-(U$5-NC1-Pad1)") (class "Default")
      (node (ref "U$5") (pin "1") (pinfunction "NC1_1") (pintype "bidirectional"))
    )
    (net (code "66") (name "unconnected-(U$5-NC3-Pad3)") (class "Default")
      (node (ref "U$5") (pin "3") (pinfunction "NC3_3") (pintype "bidirectional"))
    )
    (net (code "67") (name "unconnected-(X1-Pad3)") (class "Default")
      (node (ref "X1") (pin "3") (pinfunction "3_3") (pintype "passive"))
    )
    (net (code "68") (name "unconnected-(X1-Pad4)") (class "Default")
      (node (ref "X1") (pin "4") (pinfunction "4_4") (pintype "passive"))
    )
  )
)
